# 5V_and_3V3.net
KiCad netlist of a schematic drawn in Altium Designer
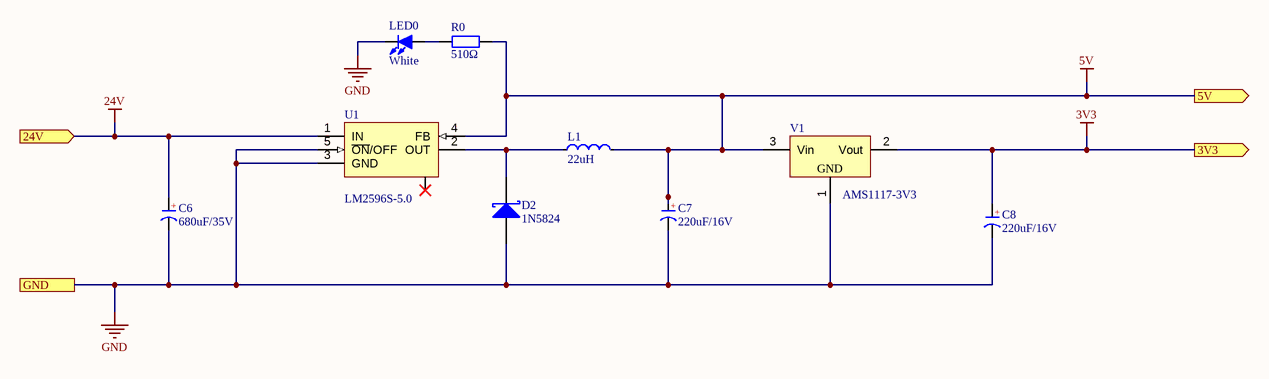
[diagram p0: 5V_and_3V3.SchDoc]

(export (version "E")
  (design (tool "Eeschema 10.0.6"))
  (components
    (comp (ref "C6")
      (value "680uF/35V")
      (footprint "CM G(12.5*13.5)")
      (description "贴片电解电容")
      (fields (field (name "版权归属") "封装库来自淘宝 ID：黄晶宝石"))
      (libsource (lib "0.1 - 电阻-电容-电感") (part "CE_SMD"))
    )
    (comp (ref "C7")
      (value "220uF/16V")
      (footprint "CM D(6.3*7.7)")
      (description "贴片电解电容 C4054381")
      (fields (field (name "版权归属") "封装库来自淘宝 ID：黄晶宝石"))
      (libsource (lib "0.1 - 电阻-电容-电感") (part "CE_SMD"))
    )
    (comp (ref "C8")
      (value "220uF/16V")
      (footprint "CM D(6.3*7.7)")
      (description "贴片电解电容 C4054381")
      (fields (field (name "版权归属") "封装库来自淘宝 ID：黄晶宝石"))
      (libsource (lib "0.1 - 电阻-电容-电感") (part "CE_SMD"))
    )
    (comp (ref "D2")
      (value "1N5824")
      (footprint "SMA")
      (description "肖特基二极管")
      (libsource (lib "0.2 - 二极管-整流桥") (part "SS14"))
    )
    (comp (ref "L1")
      (value "InductanceSMD")
      (footprint "SMD-11.5x10.5")
      (description "C280568\r\n(MHCC10040-330M-R7)")
      (fields (field (name "INDUCTANCE") "22uH"))
      (libsource (lib "CustomizedComponents") (part "InductanceSMD"))
    )
    (comp (ref "LED0")
      (value "White")
      (footprint "LED 0603W")
      (description "贴片LED")
      (fields (field (name "版权归属") "封装库来自淘宝 ID：黄晶宝石"))
      (libsource (lib "0.3 - LED发光二极管") (part "LED-SMD"))
    )
    (comp (ref "R0")
      (value "510Ω")
      (footprint "R 0603_L")
      (description "贴片电阻")
      (fields (field (name "版权归属") "来自淘宝 ID：黄晶宝石"))
      (libsource (lib "0.1 - 电阻-电容-电感") (part "R"))
    )
    (comp (ref "U1")
      (value "LM2596S-5.0")
      (footprint "TO263-5A")
      (description "5V稳压芯片")
      (fields (field (name "PUBLISHER") "Altium Limited"))
      (libsource (lib "1.1 - 电源类芯片") (part "LM2596S-5.0"))
    )
    (comp (ref "V1")
      (value "AMS1117-3V3")
      (footprint "SOT223_L")
      (description "三端稳压芯片")
      (libsource (lib "1.1 - 电源类芯片") (part "AMS1117"))
    )
  )
  (nets
    (net (code "1") (name "3V3") (class "Default")
      (node (ref "C8") (pin "1") (pinfunction "A_1") (pintype "passive"))
      (node (ref "V1") (pin "2") (pinfunction "Vout_2") (pintype "passive"))
    )
    (net (code "2") (name "5V") (class "Default")
      (node (ref "C7") (pin "1") (pinfunction "A_1") (pintype "passive"))
      (node (ref "L1") (pin "2") (pintype "passive"))
      (node (ref "R0") (pin "1") (pinfunction "1_1") (pintype "passive"))
      (node (ref "U1") (pin "4") (pinfunction "FB_4") (pintype "input"))
      (node (ref "V1") (pin "3") (pinfunction "Vin_3") (pintype "passive"))
    )
    (net (code "3") (name "24V") (class "Default")
      (node (ref "C6") (pin "1") (pinfunction "A_1") (pintype "passive"))
      (node (ref "U1") (pin "1") (pinfunction "IN_1") (pintype "power_in"))
    )
    (net (code "4") (name "GND") (class "Default")
      (node (ref "C6") (pin "2") (pinfunction "K_2") (pintype "passive"))
      (node (ref "C7") (pin "2") (pinfunction "K_2") (pintype "passive"))
      (node (ref "C8") (pin "2") (pinfunction "K_2") (pintype "passive"))
      (node (ref "D2") (pin "1") (pinfunction "A_1") (pintype "passive"))
      (node (ref "LED0") (pin "2") (pinfunction "K_2") (pintype "passive"))
      (node (ref "U1") (pin "3") (pinfunction "GND_3") (pintype "power_in"))
      (node (ref "U1") (pin "5") (pinfunction "~{ON}/OFF_5") (pintype "input"))
      (node (ref "V1") (pin "1") (pinfunction "GND_1") (pintype "passive"))
    )
    (net (code "5") (name "Net-(D2-K)") (class "Default")
      (node (ref "D2") (pin "2") (pinfunction "K_2") (pintype "passive"))
      (node (ref "L1") (pin "1") (pintype "passive"))
      (node (ref "U1") (pin "2") (pinfunction "OUT_2") (pintype "power_in"))
    )
    (net (code "6") (name "Net-(LED0-A)") (class "Default")
      (node (ref "LED0") (pin "1") (pinfunction "A_1") (pintype "passive"))
      (node (ref "R0") (pin "2") (pinfunction "2_2") (pintype "passive"))
    )
    (net (code "7") (name "unconnected-(U1-Pad6)") (class "Default")
      (node (ref "U1") (pin "6") (pinfunction "6_6") (pintype "power_in+no_connect"))
    )
  )
)
